# STM32_microcontroller_IOs.net
KiCad netlist of a schematic drawn in Altium Designer
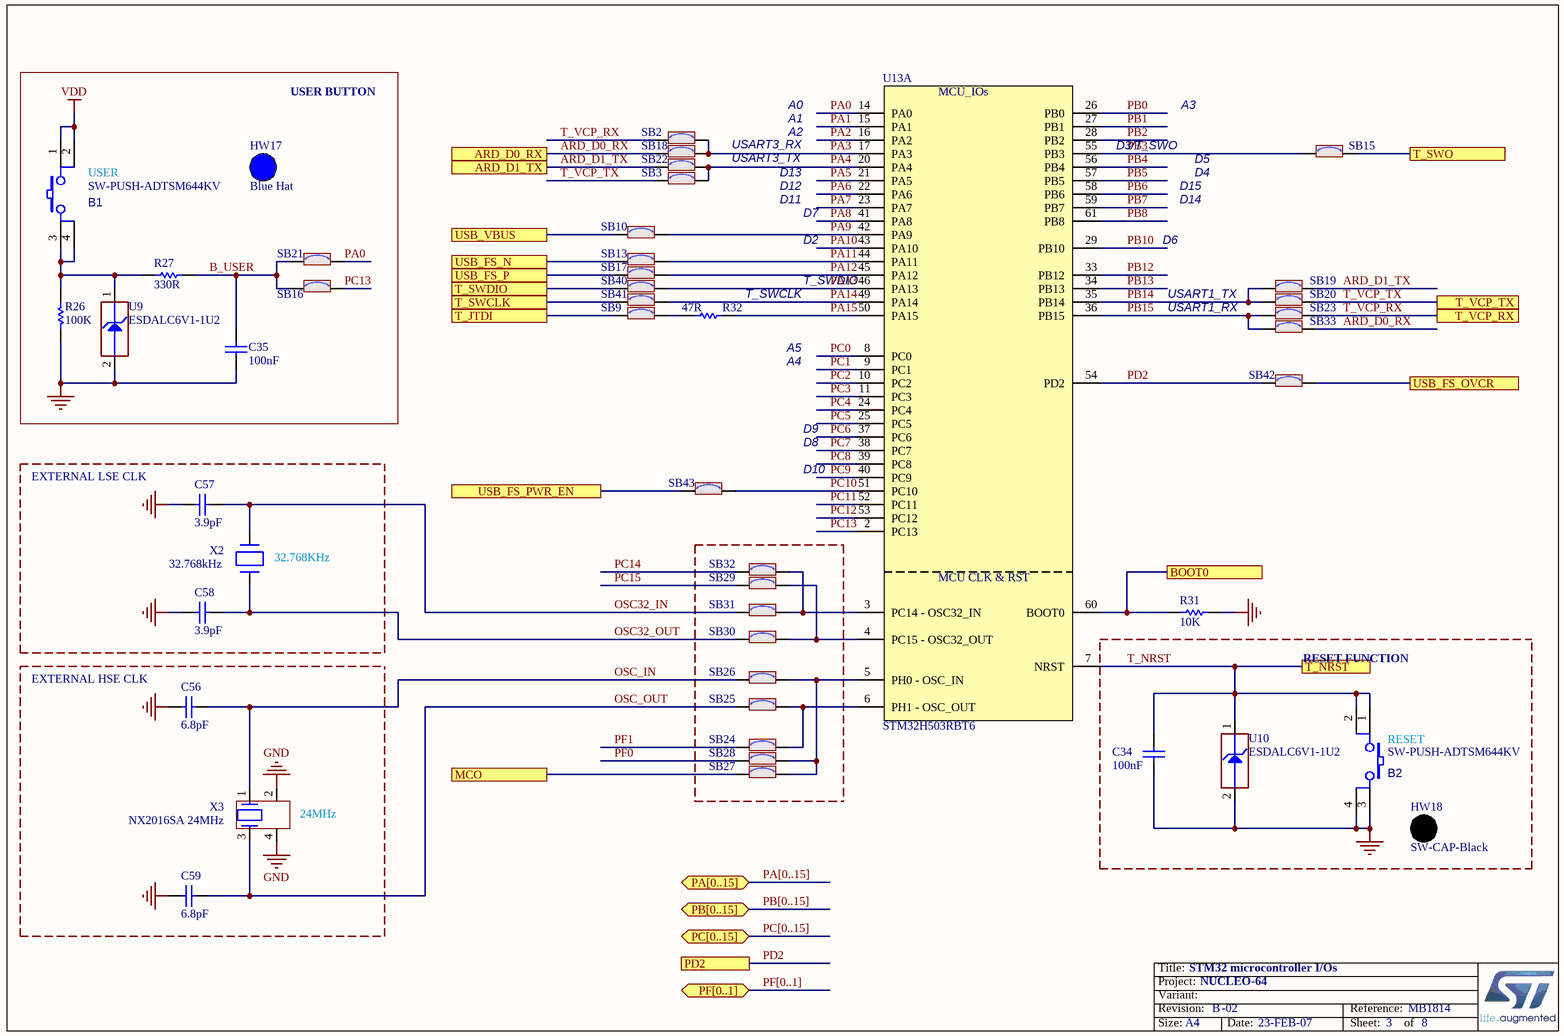
[diagram p0: STM32_microcontroller_IOs.SchDoc]

(export (version "E")
  (design (tool "Eeschema 10.0.6"))
  (components
    (comp (ref "B1")
      (value "SW-PUSH-ADTSM644KV")
      (footprint "SWI_APEM_ADTSM644KV_BLACK")
      (description "Push Button, SPST-NO, 0.05A, 12V SMT, T=7.30mm, changeable caps AKTSC62x")
      (fields (field (name "INTERNAL_PART_NUMBER") "MCD-02524") (field (name "MANUFACTURER") "APEM INC"))
      (libsource (lib "MCD_PARTS_database") (part "SW_PUSH_SMD"))
    )
    (comp (ref "B2")
      (value "SW-PUSH-ADTSM644KV")
      (footprint "SWI_APEM_ADTSM644KV_BLACK")
      (description "Push Button, SPST-NO, 0.05A, 12V SMT, T=7.30mm, changeable caps AKTSC62x")
      (fields (field (name "INTERNAL_PART_NUMBER") "MCD-02524") (field (name "MANUFACTURER") "APEM INC"))
      (libsource (lib "MCD_PARTS_database") (part "SW_PUSH_SMD"))
    )
    (comp (ref "C34")
      (value "100nF")
      (footprint "C0402")
      (description "Capacitor, MLCC, 100nF, 16V, X7R, 10%, 0402, T=0,5mm")
      (fields
        (field (name "INTERNAL_PART_NUMBER") "MCD-00102")
        (field (name "MANUFACTURER_PART_NUMBER") "CC0402KRX7R7BB104")
        (field (name "PROVIDED_BY") "Subcon")
      )
      (libsource (lib "MCD_PARTS_database") (part "Capacitor"))
    )
    (comp (ref "C35")
      (value "100nF")
      (footprint "C0402")
      (description "Capacitor, MLCC, 100nF, 16V, X7R, 10%, 0402, T=0,5mm")
      (fields
        (field (name "INTERNAL_PART_NUMBER") "MCD-00102")
        (field (name "MANUFACTURER_PART_NUMBER") "CC0402KRX7R7BB104")
        (field (name "PROVIDED_BY") "Subcon")
      )
      (libsource (lib "MCD_PARTS_database") (part "Capacitor"))
    )
    (comp (ref "C56")
      (value "6.8pF")
      (footprint "C0402")
      (description "Capacitor, MLCC, 6.8pF, 50V, NPO, +-0.25pF, 0402, T=0.5mm")
      (fields
        (field (name "INTERNAL_PART_NUMBER") "MCD-00674")
        (field (name "MANUFACTURER_PART_NUMBER") "CC0402CRNPO9BN6R8")
        (field (name "PROVIDED_BY") "SUBCO")
      )
      (libsource (lib "MCD_PARTS_database") (part "Capacitor"))
    )
    (comp (ref "C57")
      (value "3.9pF")
      (footprint "C0402")
      (description "Capacitor, MLCC, 3.9pF, 50V, NPO, +/-0.1pF, 0402, T=0.5mm")
      (fields (field (name "INTERNAL_PART_NUMBER") "MCD-01602") (field (name "MANUFACTURER") "YAGEO"))
      (libsource (lib "MCD_PARTS_database") (part "Capacitor"))
    )
    (comp (ref "C58")
      (value "3.9pF")
      (footprint "C0402")
      (description "Capacitor, MLCC, 3.9pF, 50V, NPO, +/-0.1pF, 0402, T=0.5mm")
      (fields (field (name "INTERNAL_PART_NUMBER") "MCD-01602") (field (name "MANUFACTURER") "YAGEO"))
      (libsource (lib "MCD_PARTS_database") (part "Capacitor"))
    )
    (comp (ref "C59")
      (value "6.8pF")
      (footprint "C0402")
      (description "Capacitor, MLCC, 6.8pF, 50V, NPO, +-0.25pF, 0402, T=0.5mm")
      (fields
        (field (name "INTERNAL_PART_NUMBER") "MCD-00674")
        (field (name "MANUFACTURER_PART_NUMBER") "CC0402CRNPO9BN6R8")
        (field (name "PROVIDED_BY") "SUBCO")
      )
      (libsource (lib "MCD_PARTS_database") (part "Capacitor"))
    )
    (comp (ref "HW17")
      (value "Blue Hat")
      (description "Switch hat, blue, For KTSC-62B")
      (fields (field (name "INTERNAL_PART_NUMBER") "MCD-02136") (field (name "MANUFACTURER") "APEM INC"))
      (libsource (lib "MCD_PARTS_database") (part "BUTTON_HAT_BLUE"))
    )
    (comp (ref "HW18")
      (value "SW-CAP-Black")
      (footprint "N/A")
      (description "Black round cap for ADTSM644KV")
      (fields (field (name "INTERNAL_PART_NUMBER") "MCD-02526") (field (name "MANUFACTURER") "APEM INC"))
      (libsource (lib "MCD_PARTS_database") (part "SW-CAP-Black"))
    )
    (comp (ref "R26")
      (value "100K")
      (footprint "R0603")
      (description "Resistor,100K,0603,1%,1/10W")
      (fields
        (field (name "INTERNAL_PART_NUMBER") "MCD-00223")
        (field (name "MANUFACTURER_PART_NUMBER") "RC0603FR-07100KL")
        (field (name "PROVIDED_BY") "Subcon")
      )
      (libsource (lib "MCD_PARTS_database") (part "Resistor"))
    )
    (comp (ref "R27")
      (value "330R")
      (footprint "R0603")
      (description "Resistor,330R,0603,1%,1/10W")
      (fields
        (field (name "INTERNAL_PART_NUMBER") "MCD-00197")
        (field (name "MANUFACTURER_PART_NUMBER") "RC0603FR-07330RL")
        (field (name "PROVIDED_BY") "Subcon")
      )
      (libsource (lib "MCD_PARTS_database") (part "Resistor"))
    )
    (comp (ref "R31")
      (value "10K")
      (footprint "R0603")
      (description "Resistor,10K,0603,1%,1/10W")
      (fields
        (field (name "INTERNAL_PART_NUMBER") "MCD-00220")
        (field (name "MANUFACTURER_PART_NUMBER") "RC0603FR-0710KL")
        (field (name "PROVIDED_BY") "Subcon")
      )
      (libsource (lib "MCD_PARTS_database") (part "Resistor"))
    )
    (comp (ref "R32")
      (value "47R")
      (footprint "R0402")
      (description "Resistor,47R,0402,1%,1/16W")
      (fields
        (field (name "INTERNAL_PART_NUMBER") "MCD-00481")
        (field (name "MANUFACTURER_PART_NUMBER") "RC0402FR-0747RL")
        (field (name "PROVIDED_BY") "SUBCO")
      )
      (libsource (lib "MCD_PARTS_database") (part "Resistor"))
    )
    (comp (ref "SB2")
      (value "~")
      (footprint "SOLDER-BRIDGE_R0603-0R")
      (description "Solder Bridge ON")
      (fields
        (field (name "INTERNAL_PART_NUMBER") "MCD-00071")
        (field (name "MANUFACTURER_PART_NUMBER") "RC0603JR-070RL")
        (field (name "PROVIDED_BY") "SUBCO")
      )
      (libsource (lib "") (part "SB_ON_1"))
    )
    (comp (ref "SB3")
      (value "~")
      (footprint "SOLDER-BRIDGE_R0603-0R")
      (description "Solder Bridge ON")
      (fields
        (field (name "INTERNAL_PART_NUMBER") "MCD-00071")
        (field (name "MANUFACTURER_PART_NUMBER") "RC0603JR-070RL")
        (field (name "PROVIDED_BY") "SUBCO")
      )
      (libsource (lib "") (part "SB_ON_1"))
    )
    (comp (ref "SB9")
      (value "~")
      (footprint "SOLDER-BRIDGE_R0603-0R")
      (description "Solder Bridge ON")
      (fields
        (field (name "INTERNAL_PART_NUMBER") "MCD-00071")
        (field (name "MANUFACTURER_PART_NUMBER") "RC0603JR-070RL")
        (field (name "PROVIDED_BY") "SUBCO")
      )
      (libsource (lib "MCD_PARTS_database") (part "SB_ON"))
    )
    (comp (ref "SB10")
      (value "~")
      (footprint "SOLDER-BRIDGE_R0603-0R")
      (description "Solder Bridge ON")
      (fields
        (field (name "INTERNAL_PART_NUMBER") "MCD-00071")
        (field (name "MANUFACTURER_PART_NUMBER") "RC0603JR-070RL")
        (field (name "PROVIDED_BY") "SUBCO")
      )
      (libsource (lib "MCD_PARTS_database") (part "SB_ON"))
    )
    (comp (ref "SB13")
      (value "~")
      (footprint "SOLDER-BRIDGE_R0603-0R")
      (description "Solder Bridge ON")
      (fields
        (field (name "INTERNAL_PART_NUMBER") "MCD-00071")
        (field (name "MANUFACTURER_PART_NUMBER") "RC0603JR-070RL")
        (field (name "PROVIDED_BY") "SUBCO")
      )
      (libsource (lib "MCD_PARTS_database") (part "SB_ON"))
    )
    (comp (ref "SB15")
      (value "~")
      (footprint "SOLDER-BRIDGE_R0603-0R")
      (description "Solder Bridge ON")
      (fields
        (field (name "INTERNAL_PART_NUMBER") "MCD-00071")
        (field (name "MANUFACTURER_PART_NUMBER") "RC0603JR-070RL")
        (field (name "PROVIDED_BY") "SUBCO")
      )
      (libsource (lib "MCD_PARTS_database") (part "SB_ON"))
    )
    (comp (ref "SB16")
      (value "~")
      (footprint "SOLDER-BRIDGE_R0603-0R")
      (description "Solder Bridge ON")
      (fields
        (field (name "INTERNAL_PART_NUMBER") "MCD-00071")
        (field (name "MANUFACTURER_PART_NUMBER") "RC0603JR-070RL")
        (field (name "PROVIDED_BY") "SUBCO")
      )
      (libsource (lib "MCD_PARTS_database") (part "SB_ON"))
    )
    (comp (ref "SB17")
      (value "~")
      (footprint "SOLDER-BRIDGE_R0603-0R")
      (description "Solder Bridge ON")
      (fields
        (field (name "INTERNAL_PART_NUMBER") "MCD-00071")
        (field (name "MANUFACTURER_PART_NUMBER") "RC0603JR-070RL")
        (field (name "PROVIDED_BY") "SUBCO")
      )
      (libsource (lib "MCD_PARTS_database") (part "SB_ON"))
    )
    (comp (ref "SB18")
      (value "~")
      (footprint "SOLDER-BRIDGE_R0603-0R")
      (description "Solder Bridge ON")
      (fields
        (field (name "INTERNAL_PART_NUMBER") "MCD-00071")
        (field (name "MANUFACTURER_PART_NUMBER") "RC0603JR-070RL")
        (field (name "PROVIDED_BY") "SUBCO")
      )
      (libsource (lib "") (part "SB_ON_1"))
    )
    (comp (ref "SB19")
      (value "~")
      (footprint "SOLDER-BRIDGE_R0603-0R")
      (description "Solder Bridge ON")
      (fields
        (field (name "INTERNAL_PART_NUMBER") "MCD-00071")
        (field (name "MANUFACTURER_PART_NUMBER") "RC0603JR-070RL")
        (field (name "PROVIDED_BY") "SUBCO")
      )
      (libsource (lib "") (part "SB_ON_1"))
    )
    (comp (ref "SB20")
      (value "~")
      (footprint "SOLDER-BRIDGE_R0603-0R")
      (description "Solder Bridge ON")
      (fields
        (field (name "INTERNAL_PART_NUMBER") "MCD-00071")
        (field (name "MANUFACTURER_PART_NUMBER") "RC0603JR-070RL")
        (field (name "PROVIDED_BY") "SUBCO")
      )
      (libsource (lib "") (part "SB_ON_1"))
    )
    (comp (ref "SB21")
      (value "~")
      (footprint "SOLDER-BRIDGE_R0603-0R")
      (description "Solder Bridge ON")
      (fields
        (field (name "INTERNAL_PART_NUMBER") "MCD-00071")
        (field (name "MANUFACTURER_PART_NUMBER") "RC0603JR-070RL")
        (field (name "PROVIDED_BY") "SUBCO")
      )
      (libsource (lib "MCD_PARTS_database") (part "SB_ON"))
    )
    (comp (ref "SB22")
      (value "~")
      (footprint "SOLDER-BRIDGE_R0603-0R")
      (description "Solder Bridge ON")
      (fields
        (field (name "INTERNAL_PART_NUMBER") "MCD-00071")
        (field (name "MANUFACTURER_PART_NUMBER") "RC0603JR-070RL")
        (field (name "PROVIDED_BY") "SUBCO")
      )
      (libsource (lib "") (part "SB_ON_1"))
    )
    (comp (ref "SB23")
      (value "~")
      (footprint "SOLDER-BRIDGE_R0603-0R")
      (description "Solder Bridge ON")
      (fields
        (field (name "INTERNAL_PART_NUMBER") "MCD-00071")
        (field (name "MANUFACTURER_PART_NUMBER") "RC0603JR-070RL")
        (field (name "PROVIDED_BY") "SUBCO")
      )
      (libsource (lib "") (part "SB_ON_1"))
    )
    (comp (ref "SB24")
      (value "~")
      (footprint "SOLDER-BRIDGE_R0603-0R")
      (description "Solder Bridge ON")
      (fields
        (field (name "INTERNAL_PART_NUMBER") "MCD-00071")
        (field (name "MANUFACTURER_PART_NUMBER") "RC0603JR-070RL")
        (field (name "PROVIDED_BY") "SUBCO")
      )
      (libsource (lib "MCD_PARTS_database") (part "SB_ON"))
    )
    (comp (ref "SB25")
      (value "~")
      (footprint "SOLDER-BRIDGE_R0603-0R")
      (description "Solder Bridge ON")
      (fields
        (field (name "INTERNAL_PART_NUMBER") "MCD-00071")
        (field (name "MANUFACTURER_PART_NUMBER") "RC0603JR-070RL")
        (field (name "PROVIDED_BY") "SUBCO")
      )
      (libsource (lib "MCD_PARTS_database") (part "SB_ON"))
    )
    (comp (ref "SB26")
      (value "~")
      (footprint "SOLDER-BRIDGE_R0603-0R")
      (description "Solder Bridge ON")
      (fields
        (field (name "INTERNAL_PART_NUMBER") "MCD-00071")
        (field (name "MANUFACTURER_PART_NUMBER") "RC0603JR-070RL")
        (field (name "PROVIDED_BY") "SUBCO")
      )
      (libsource (lib "MCD_PARTS_database") (part "SB_ON"))
    )
    (comp (ref "SB27")
      (value "~")
      (footprint "SOLDER-BRIDGE_R0603-0R")
      (description "Solder Bridge ON")
      (fields
        (field (name "INTERNAL_PART_NUMBER") "MCD-00071")
        (field (name "MANUFACTURER_PART_NUMBER") "RC0603JR-070RL")
        (field (name "PROVIDED_BY") "SUBCO")
      )
      (libsource (lib "MCD_PARTS_database") (part "SB_ON"))
    )
    (comp (ref "SB28")
      (value "~")
      (footprint "SOLDER-BRIDGE_R0603-0R")
      (description "Solder Bridge ON")
      (fields
        (field (name "INTERNAL_PART_NUMBER") "MCD-00071")
        (field (name "MANUFACTURER_PART_NUMBER") "RC0603JR-070RL")
        (field (name "PROVIDED_BY") "SUBCO")
      )
      (libsource (lib "MCD_PARTS_database") (part "SB_ON"))
    )
    (comp (ref "SB29")
      (value "~")
      (footprint "SOLDER-BRIDGE_R0603-0R")
      (description "Solder Bridge ON")
      (fields
        (field (name "INTERNAL_PART_NUMBER") "MCD-00071")
        (field (name "MANUFACTURER_PART_NUMBER") "RC0603JR-070RL")
        (field (name "PROVIDED_BY") "SUBCO")
      )
      (libsource (lib "MCD_PARTS_database") (part "SB_ON"))
    )
    (comp (ref "SB30")
      (value "~")
      (footprint "SOLDER-BRIDGE_R0603-0R")
      (description "Solder Bridge ON")
      (fields
        (field (name "INTERNAL_PART_NUMBER") "MCD-00071")
        (field (name "MANUFACTURER_PART_NUMBER") "RC0603JR-070RL")
        (field (name "PROVIDED_BY") "SUBCO")
      )
      (libsource (lib "MCD_PARTS_database") (part "SB_ON"))
    )
    (comp (ref "SB31")
      (value "~")
      (footprint "SOLDER-BRIDGE_R0603-0R")
      (description "Solder Bridge ON")
      (fields
        (field (name "INTERNAL_PART_NUMBER") "MCD-00071")
        (field (name "MANUFACTURER_PART_NUMBER") "RC0603JR-070RL")
        (field (name "PROVIDED_BY") "SUBCO")
      )
      (libsource (lib "MCD_PARTS_database") (part "SB_ON"))
    )
    (comp (ref "SB32")
      (value "~")
      (footprint "SOLDER-BRIDGE_R0603-0R")
      (description "Solder Bridge ON")
      (fields
        (field (name "INTERNAL_PART_NUMBER") "MCD-00071")
        (field (name "MANUFACTURER_PART_NUMBER") "RC0603JR-070RL")
        (field (name "PROVIDED_BY") "SUBCO")
      )
      (libsource (lib "MCD_PARTS_database") (part "SB_ON"))
    )
    (comp (ref "SB33")
      (value "~")
      (footprint "SOLDER-BRIDGE_R0603-0R")
      (description "Solder Bridge ON")
      (fields
        (field (name "INTERNAL_PART_NUMBER") "MCD-00071")
        (field (name "MANUFACTURER_PART_NUMBER") "RC0603JR-070RL")
        (field (name "PROVIDED_BY") "SUBCO")
      )
      (libsource (lib "") (part "SB_ON_1"))
    )
    (comp (ref "SB40")
      (value "~")
      (footprint "SOLDER-BRIDGE_R0603-0R")
      (description "Solder Bridge ON")
      (fields
        (field (name "INTERNAL_PART_NUMBER") "MCD-00071")
        (field (name "MANUFACTURER_PART_NUMBER") "RC0603JR-070RL")
        (field (name "PROVIDED_BY") "SUBCO")
      )
      (libsource (lib "MCD_PARTS_database") (part "SB_ON"))
    )
    (comp (ref "SB41")
      (value "~")
      (footprint "SOLDER-BRIDGE_R0603-0R")
      (description "Solder Bridge ON")
      (fields
        (field (name "INTERNAL_PART_NUMBER") "MCD-00071")
        (field (name "MANUFACTURER_PART_NUMBER") "RC0603JR-070RL")
        (field (name "PROVIDED_BY") "SUBCO")
      )
      (libsource (lib "MCD_PARTS_database") (part "SB_ON"))
    )
    (comp (ref "SB42")
      (value "~")
      (footprint "SOLDER-BRIDGE_R0603-0R")
      (description "Solder Bridge ON")
      (fields
        (field (name "INTERNAL_PART_NUMBER") "MCD-00071")
        (field (name "MANUFACTURER_PART_NUMBER") "RC0603JR-070RL")
        (field (name "PROVIDED_BY") "SUBCO")
      )
      (libsource (lib "MCD_PARTS_database") (part "SB_ON"))
    )
    (comp (ref "SB43")
      (value "~")
      (footprint "SOLDER-BRIDGE_R0603-0R")
      (description "Solder Bridge ON")
      (fields
        (field (name "INTERNAL_PART_NUMBER") "MCD-00071")
        (field (name "MANUFACTURER_PART_NUMBER") "RC0603JR-070RL")
        (field (name "PROVIDED_BY") "SUBCO")
      )
      (libsource (lib "MCD_PARTS_database") (part "SB_ON"))
    )
    (comp (ref "U9")
      (value "ESDALC6V1-1U2")
      (footprint "ESD_ST0201")
      (description "ESD protection 6V1")
      (fields
        (field (name "INTERNAL_PART_NUMBER") "MCD-00170")
        (field (name "MANUFACTURER") "STMICROELECTRONICS")
        (field (name "PROVIDED_BY") "Subcon")
      )
      (libsource (lib "MCD_PARTS_database") (part "ESD-TRANSIL"))
    )
    (comp (ref "U10")
      (value "ESDALC6V1-1U2")
      (footprint "ESD_ST0201")
      (description "ESD protection 6V1")
      (fields
        (field (name "INTERNAL_PART_NUMBER") "MCD-00170")
        (field (name "MANUFACTURER") "STMICROELECTRONICS")
        (field (name "PROVIDED_BY") "Subcon")
      )
      (libsource (lib "MCD_PARTS_database") (part "ESD-TRANSIL"))
    )
    (comp (ref "U13")
      (value "STM32H503RBT6")
      (footprint "ICC_LQFP64_10X10_P050_SOCKET_YAMAICHI_IC149-064-069-B5_NM")
      (description "MCU, Arm Cortex-M33, 250MHz, 32-bit MCU, 128KB flash, 32KB SRAM")
      (fields
        (field (name "INTERNAL_PART_NUMBER") "MCD-02438")
        (field (name "MANUFACTURER") "STMICROELECTRONICS")
      )
      (libsource (lib "MCD_PARTS_database") (part "STM32H503RBH6"))
    )
    (comp (ref "X2")
      (value "32.768kHz")
      (footprint "CRY_NX1610SE_2P")
      (description "Crystal, 32.768kHz, 9pF, +/-20ppm, 70KR, 1.6x1mm")
      (fields (field (name "INTERNAL_PART_NUMBER") "MCD-02291") (field (name "MANUFACTURER") "NDK"))
      (libsource (lib "MCD_PARTS_database") (part "XTAL_2_PINS"))
    )
    (comp (ref "X3")
      (value "NX2016SA 24MHz")
      (footprint "CRY_NX2016SA_4P")
      (description "Crystal 24MHz, 6pF, +-20ppm, 80ohms max, SMD")
      (fields
        (field (name "INTERNAL_PART_NUMBER") "MCD-01036")
        (field (name "MANUFACTURER_PART_NUMBER") "NX2016SA 24MHz EXS00A-CS10820")
        (field (name "PROVIDED_BY") "SUBCO")
      )
      (libsource (lib "MCD_PARTS_database") (part "XTAL_4_PINS"))
    )
  )
  (nets
    (net (code "3") (name "/ARD_D0_RX") (class "Default")
      (node (ref "SB18") (pin "2") (pinfunction "2_2") (pintype "passive"))
      (node (ref "SB33") (pin "1") (pinfunction "1_1") (pintype "passive"))
    )
    (net (code "4") (name "/ARD_D1_TX") (class "Default")
      (node (ref "SB19") (pin "1") (pinfunction "1_1") (pintype "passive"))
      (node (ref "SB22") (pin "2") (pinfunction "2_2") (pintype "passive"))
    )
    (net (code "5") (name "/BOOT0") (class "Default")
      (node (ref "R31") (pin "2") (pinfunction "2_2") (pintype "passive"))
      (node (ref "U13") (pin "60") (pinfunction "BOOT0_60") (pintype "passive"))
    )
    (net (code "6") (name "/B_USER") (class "Default")
      (node (ref "C35") (pin "2") (pinfunction "2_2") (pintype "passive"))
      (node (ref "R27") (pin "2") (pinfunction "2_2") (pintype "passive"))
      (node (ref "SB16") (pin "1") (pinfunction "1_1") (pintype "passive"))
      (node (ref "SB21") (pin "1") (pinfunction "1_1") (pintype "passive"))
    )
    (net (code "7") (name "/MCO") (class "Default")
      (node (ref "SB27") (pin "1") (pinfunction "1_1") (pintype "passive"))
    )
    (net (code "8") (name "/OSC32_IN") (class "Default")
      (node (ref "C57") (pin "2") (pinfunction "2_2") (pintype "passive"))
      (node (ref "SB31") (pin "1") (pinfunction "1_1") (pintype "passive"))
      (node (ref "X2") (pin "2") (pinfunction "X2_2") (pintype "passive"))
    )
    (net (code "9") (name "/OSC32_OUT") (class "Default")
      (node (ref "C58") (pin "2") (pinfunction "2_2") (pintype "passive"))
      (node (ref "SB30") (pin "1") (pinfunction "1_1") (pintype "passive"))
      (node (ref "X2") (pin "1") (pinfunction "X1_1") (pintype "passive"))
    )
    (net (code "10") (name "/OSC_IN") (class "Default")
      (node (ref "C56") (pin "2") (pinfunction "2_2") (pintype "passive"))
      (node (ref "SB26") (pin "1") (pinfunction "1_1") (pintype "passive"))
      (node (ref "X3") (pin "1") (pinfunction "1_1") (pintype "passive"))
    )
    (net (code "11") (name "/OSC_OUT") (class "Default")
      (node (ref "C59") (pin "2") (pinfunction "2_2") (pintype "passive"))
      (node (ref "SB25") (pin "1") (pinfunction "1_1") (pintype "passive"))
      (node (ref "X3") (pin "3") (pinfunction "3_3") (pintype "passive"))
    )
    (net (code "12") (name "/PA0") (class "Default")
      (node (ref "SB21") (pin "2") (pinfunction "2_2") (pintype "passive"))
      (node (ref "U13") (pin "14") (pinfunction "PA0_14") (pintype "passive"))
    )
    (net (code "13") (name "/PA1") (class "Default")
      (node (ref "U13") (pin "15") (pinfunction "PA1_15") (pintype "passive"))
    )
    (net (code "14") (name "/PA2") (class "Default")
      (node (ref "U13") (pin "16") (pinfunction "PA2_16") (pintype "passive"))
    )
    (net (code "15") (name "/PA3") (class "Default")
      (node (ref "SB18") (pin "1") (pinfunction "1_1") (pintype "passive"))
      (node (ref "SB2") (pin "1") (pinfunction "1_1") (pintype "passive"))
      (node (ref "U13") (pin "17") (pinfunction "PA3_17") (pintype "passive"))
    )
    (net (code "16") (name "/PA4") (class "Default")
      (node (ref "SB22") (pin "1") (pinfunction "1_1") (pintype "passive"))
      (node (ref "SB3") (pin "1") (pinfunction "1_1") (pintype "passive"))
      (node (ref "U13") (pin "20") (pinfunction "PA4_20") (pintype "passive"))
    )
    (net (code "17") (name "/PA5") (class "Default")
      (node (ref "U13") (pin "21") (pinfunction "PA5_21") (pintype "passive"))
    )
    (net (code "18") (name "/PA6") (class "Default")
      (node (ref "U13") (pin "22") (pinfunction "PA6_22") (pintype "passive"))
    )
    (net (code "19") (name "/PA7") (class "Default")
      (node (ref "U13") (pin "23") (pinfunction "PA7_23") (pintype "passive"))
    )
    (net (code "20") (name "/PA8") (class "Default")
      (node (ref "U13") (pin "41") (pinfunction "PA8_41") (pintype "passive"))
    )
    (net (code "21") (name "/PA9") (class "Default")
      (node (ref "SB10") (pin "2") (pinfunction "2_2") (pintype "passive"))
      (node (ref "U13") (pin "42") (pinfunction "PA9_42") (pintype "passive"))
    )
    (net (code "22") (name "/PA10") (class "Default")
      (node (ref "U13") (pin "43") (pinfunction "PA10_43") (pintype "passive"))
    )
    (net (code "23") (name "/PA11") (class "Default")
      (node (ref "SB13") (pin "2") (pinfunction "2_2") (pintype "passive"))
      (node (ref "U13") (pin "44") (pinfunction "PA11_44") (pintype "passive"))
    )
    (net (code "24") (name "/PA12") (class "Default")
      (node (ref "SB17") (pin "2") (pinfunction "2_2") (pintype "passive"))
      (node (ref "U13") (pin "45") (pinfunction "PA12_45") (pintype "passive"))
    )
    (net (code "25") (name "/PA13") (class "Default")
      (node (ref "SB40") (pin "2") (pinfunction "2_2") (pintype "passive"))
      (node (ref "U13") (pin "46") (pinfunction "PA13_46") (pintype "passive"))
    )
    (net (code "26") (name "/PA14") (class "Default")
      (node (ref "SB41") (pin "2") (pinfunction "2_2") (pintype "passive"))
      (node (ref "U13") (pin "49") (pinfunction "PA14_49") (pintype "passive"))
    )
    (net (code "27") (name "/PA15") (class "Default")
      (node (ref "R32") (pin "2") (pinfunction "2_2") (pintype "passive"))
      (node (ref "U13") (pin "50") (pinfunction "PA15_50") (pintype "passive"))
    )
    (net (code "29") (name "/PB0") (class "Default")
      (node (ref "U13") (pin "26") (pinfunction "PB0_26") (pintype "passive"))
    )
    (net (code "30") (name "/PB1") (class "Default")
      (node (ref "U13") (pin "27") (pinfunction "PB1_27") (pintype "passive"))
    )
    (net (code "31") (name "/PB2") (class "Default")
      (node (ref "U13") (pin "28") (pinfunction "PB2_28") (pintype "passive"))
    )
    (net (code "32") (name "/PB3") (class "Default")
      (node (ref "SB15") (pin "1") (pinfunction "1_1") (pintype "passive"))
      (node (ref "U13") (pin "55") (pinfunction "PB3_55") (pintype "passive"))
    )
    (net (code "33") (name "/PB4") (class "Default")
      (node (ref "U13") (pin "56") (pinfunction "PB4_56") (pintype "passive"))
    )
    (net (code "34") (name "/PB5") (class "Default")
      (node (ref "U13") (pin "57") (pinfunction "PB5_57") (pintype "passive"))
    )
    (net (code "35") (name "/PB6") (class "Default")
      (node (ref "U13") (pin "58") (pinfunction "PB6_58") (pintype "passive"))
    )
    (net (code "36") (name "/PB7") (class "Default")
      (node (ref "U13") (pin "59") (pinfunction "PB7_59") (pintype "passive"))
    )
    (net (code "37") (name "/PB8") (class "Default")
      (node (ref "U13") (pin "61") (pinfunction "PB8_61") (pintype "passive"))
    )
    (net (code "38") (name "/PB10") (class "Default")
      (node (ref "U13") (pin "29") (pinfunction "PB10_29") (pintype "passive"))
    )
    (net (code "39") (name "/PB12") (class "Default")
      (node (ref "U13") (pin "33") (pinfunction "PB12_33") (pintype "passive"))
    )
    (net (code "40") (name "/PB13") (class "Default")
      (node (ref "U13") (pin "34") (pinfunction "PB13_34") (pintype "passive"))
    )
    (net (code "41") (name "/PB14") (class "Default")
      (node (ref "SB19") (pin "2") (pinfunction "2_2") (pintype "passive"))
      (node (ref "SB20") (pin "2") (pinfunction "2_2") (pintype "passive"))
      (node (ref "U13") (pin "35") (pinfunction "PB14_35") (pintype "passive"))
    )
    (net (code "42") (name "/PB15") (class "Default")
      (node (ref "SB23") (pin "2") (pinfunction "2_2") (pintype "passive"))
      (node (ref "SB33") (pin "2") (pinfunction "2_2") (pintype "passive"))
      (node (ref "U13") (pin "36") (pinfunction "PB15_36") (pintype "passive"))
    )
    (net (code "44") (name "/PC0") (class "Default")
      (node (ref "U13") (pin "8") (pinfunction "PC0_8") (pintype "passive"))
    )
    (net (code "45") (name "/PC1") (class "Default")
      (node (ref "U13") (pin "9") (pinfunction "PC1_9") (pintype "passive"))
    )
    (net (code "46") (name "/PC2") (class "Default")
      (node (ref "U13") (pin "10") (pinfunction "PC2_10") (pintype "passive"))
    )
    (net (code "47") (name "/PC3") (class "Default")
      (node (ref "U13") (pin "11") (pinfunction "PC3_11") (pintype "passive"))
    )
    (net (code "48") (name "/PC4") (class "Default")
      (node (ref "U13") (pin "24") (pinfunction "PC4_24") (pintype "passive"))
    )
    (net (code "49") (name "/PC5") (class "Default")
      (node (ref "U13") (pin "25") (pinfunction "PC5_25") (pintype "passive"))
    )
    (net (code "50") (name "/PC6") (class "Default")
      (node (ref "U13") (pin "37") (pinfunction "PC6_37") (pintype "passive"))
    )
    (net (code "51") (name "/PC7") (class "Default")
      (node (ref "U13") (pin "38") (pinfunction "PC7_38") (pintype "passive"))
    )
    (net (code "52") (name "/PC8") (class "Default")
      (node (ref "U13") (pin "39") (pinfunction "PC8_39") (pintype "passive"))
    )
    (net (code "53") (name "/PC9") (class "Default")
      (node (ref "U13") (pin "40") (pinfunction "PC9_40") (pintype "passive"))
    )
    (net (code "54") (name "/PC10") (class "Default")
      (node (ref "SB43") (pin "2") (pinfunction "2_2") (pintype "passive"))
      (node (ref "U13") (pin "51") (pinfunction "PC10_51") (pintype "passive"))
    )
    (net (code "55") (name "/PC11") (class "Default")
      (node (ref "U13") (pin "52") (pinfunction "PC11_52") (pintype "passive"))
    )
    (net (code "56") (name "/PC12") (class "Default")
      (node (ref "U13") (pin "53") (pinfunction "PC12_53") (pintype "passive"))
    )
    (net (code "57") (name "/PC13") (class "Default")
      (node (ref "SB16") (pin "2") (pinfunction "2_2") (pintype "passive"))
      (node (ref "U13") (pin "2") (pinfunction "PC13_2") (pintype "passive"))
    )
    (net (code "58") (name "/PC14") (class "Default")
      (node (ref "SB32") (pin "1") (pinfunction "1_1") (pintype "passive"))
    )
    (net (code "59") (name "/PC15") (class "Default")
      (node (ref "SB29") (pin "1") (pinfunction "1_1") (pintype "passive"))
    )
    (net (code "61") (name "/PD2") (class "Default")
      (node (ref "SB42") (pin "1") (pinfunction "1_1") (pintype "passive"))
      (node (ref "U13") (pin "54") (pinfunction "PD2_54") (pintype "passive"))
    )
    (net (code "62") (name "/PF0") (class "Default")
      (node (ref "SB28") (pin "1") (pinfunction "1_1") (pintype "passive"))
    )
    (net (code "63") (name "/PF1") (class "Default")
      (node (ref "SB24") (pin "1") (pinfunction "1_1") (pintype "passive"))
    )
    (net (code "65") (name "/T_JTDI") (class "Default")
      (node (ref "SB9") (pin "1") (pinfunction "1_1") (pintype "passive"))
    )
    (net (code "66") (name "/T_NRST") (class "Default")
      (node (ref "B2") (pin "1") (pinfunction "1_1") (pintype "passive"))
      (node (ref "B2") (pin "2") (pinfunction "2_2") (pintype "passive"))
      (node (ref "C34") (pin "2") (pinfunction "2_2") (pintype "passive"))
      (node (ref "U10") (pin "1") (pinfunction "IO1_1") (pintype "passive"))
      (node (ref "U13") (pin "7") (pinfunction "NRST_7") (pintype "passive"))
    )
    (net (code "67") (name "/T_SWCLK") (class "Default")
      (node (ref "SB41") (pin "1") (pinfunction "1_1") (pintype "passive"))
    )
    (net (code "68") (name "/T_SWDIO") (class "Default")
      (node (ref "SB40") (pin "1") (pinfunction "1_1") (pintype "passive"))
    )
    (net (code "69") (name "/T_SWO") (class "Default")
      (node (ref "SB15") (pin "2") (pinfunction "2_2") (pintype "passive"))
    )
    (net (code "70") (name "/T_VCP_RX") (class "Default")
      (node (ref "SB2") (pin "2") (pinfunction "2_2") (pintype "passive"))
      (node (ref "SB23") (pin "1") (pinfunction "1_1") (pintype "passive"))
    )
    (net (code "71") (name "/T_VCP_TX") (class "Default")
      (node (ref "SB20") (pin "1") (pinfunction "1_1") (pintype "passive"))
      (node (ref "SB3") (pin "2") (pinfunction "2_2") (pintype "passive"))
    )
    (net (code "72") (name "/USB_FS_N") (class "Default")
      (node (ref "SB13") (pin "1") (pinfunction "1_1") (pintype "passive"))
    )
    (net (code "73") (name "/USB_FS_OVCR") (class "Default")
      (node (ref "SB42") (pin "2") (pinfunction "2_2") (pintype "passive"))
    )
    (net (code "74") (name "/USB_FS_P") (class "Default")
      (node (ref "SB17") (pin "1") (pinfunction "1_1") (pintype "passive"))
    )
    (net (code "75") (name "/USB_FS_PWR_EN") (class "Default")
      (node (ref "SB43") (pin "1") (pinfunction "1_1") (pintype "passive"))
    )
    (net (code "76") (name "/USB_VBUS") (class "Default")
      (node (ref "SB10") (pin "1") (pinfunction "1_1") (pintype "passive"))
    )
    (net (code "77") (name "GND") (class "Default")
      (node (ref "B2") (pin "3") (pinfunction "3_3") (pintype "passive"))
      (node (ref "B2") (pin "4") (pinfunction "4_4") (pintype "passive"))
      (node (ref "C34") (pin "1") (pinfunction "1_1") (pintype "passive"))
      (node (ref "C35") (pin "1") (pinfunction "1_1") (pintype "passive"))
      (node (ref "C56") (pin "1") (pinfunction "1_1") (pintype "passive"))
      (node (ref "C57") (pin "1") (pinfunction "1_1") (pintype "passive"))
      (node (ref "C58") (pin "1") (pinfunction "1_1") (pintype "passive"))
      (node (ref "C59") (pin "1") (pinfunction "1_1") (pintype "passive"))
      (node (ref "R26") (pin "1") (pinfunction "1_1") (pintype "passive"))
      (node (ref "R31") (pin "1") (pinfunction "1_1") (pintype "passive"))
      (node (ref "U10") (pin "2") (pinfunction "GND_2") (pintype "passive"))
      (node (ref "U9") (pin "2") (pinfunction "GND_2") (pintype "passive"))
      (node (ref "X3") (pin "2") (pinfunction "2_2") (pintype "passive"))
      (node (ref "X3") (pin "4") (pinfunction "4_4") (pintype "passive"))
    )
    (net (code "78") (name "Net-(R32-Pad1)") (class "Default")
      (node (ref "R32") (pin "1") (pinfunction "1_1") (pintype "passive"))
      (node (ref "SB9") (pin "2") (pinfunction "2_2") (pintype "passive"))
    )
    (net (code "79") (name "Net-(U9-IO1)") (class "Default")
      (node (ref "B1") (pin "3") (pinfunction "3_3") (pintype "passive"))
      (node (ref "B1") (pin "4") (pinfunction "4_4") (pintype "passive"))
      (node (ref "R26") (pin "2") (pinfunction "2_2") (pintype "passive"))
      (node (ref "R27") (pin "1") (pinfunction "1_1") (pintype "passive"))
      (node (ref "U9") (pin "1") (pinfunction "IO1_1") (pintype "passive"))
    )
    (net (code "80") (name "Net-(U13A-PC14_-_OSC32_IN)") (class "Default")
      (node (ref "SB31") (pin "2") (pinfunction "2_2") (pintype "passive"))
      (node (ref "SB32") (pin "2") (pinfunction "2_2") (pintype "passive"))
      (node (ref "U13") (pin "3") (pinfunction "PC14_-_OSC32_IN_3") (pintype "passive"))
    )
    (net (code "81") (name "Net-(U13A-PC15_-_OSC32_OUT)") (class "Default")
      (node (ref "SB29") (pin "2") (pinfunction "2_2") (pintype "passive"))
      (node (ref "SB30") (pin "2") (pinfunction "2_2") (pintype "passive"))
      (node (ref "U13") (pin "4") (pinfunction "PC15_-_OSC32_OUT_4") (pintype "passive"))
    )
    (net (code "82") (name "Net-(U13A-PH0_-_OSC_IN)") (class "Default")
      (node (ref "SB26") (pin "2") (pinfunction "2_2") (pintype "passive"))
      (node (ref "SB27") (pin "2") (pinfunction "2_2") (pintype "passive"))
      (node (ref "SB28") (pin "2") (pinfunction "2_2") (pintype "passive"))
      (node (ref "U13") (pin "5") (pinfunction "PH0_-_OSC_IN_5") (pintype "passive"))
    )
    (net (code "83") (name "Net-(U13A-PH1_-_OSC_OUT)") (class "Default")
      (node (ref "SB24") (pin "2") (pinfunction "2_2") (pintype "passive"))
      (node (ref "SB25") (pin "2") (pinfunction "2_2") (pintype "passive"))
      (node (ref "U13") (pin "6") (pinfunction "PH1_-_OSC_OUT_6") (pintype "passive"))
    )
    (net (code "84") (name "VDD") (class "Default")
      (node (ref "B1") (pin "1") (pinfunction "1_1") (pintype "passive"))
      (node (ref "B1") (pin "2") (pinfunction "2_2") (pintype "passive"))
    )
  )
)
